# Easycheck_rev2_motherboard.net
KiCad netlist of a schematic drawn in EAGLE
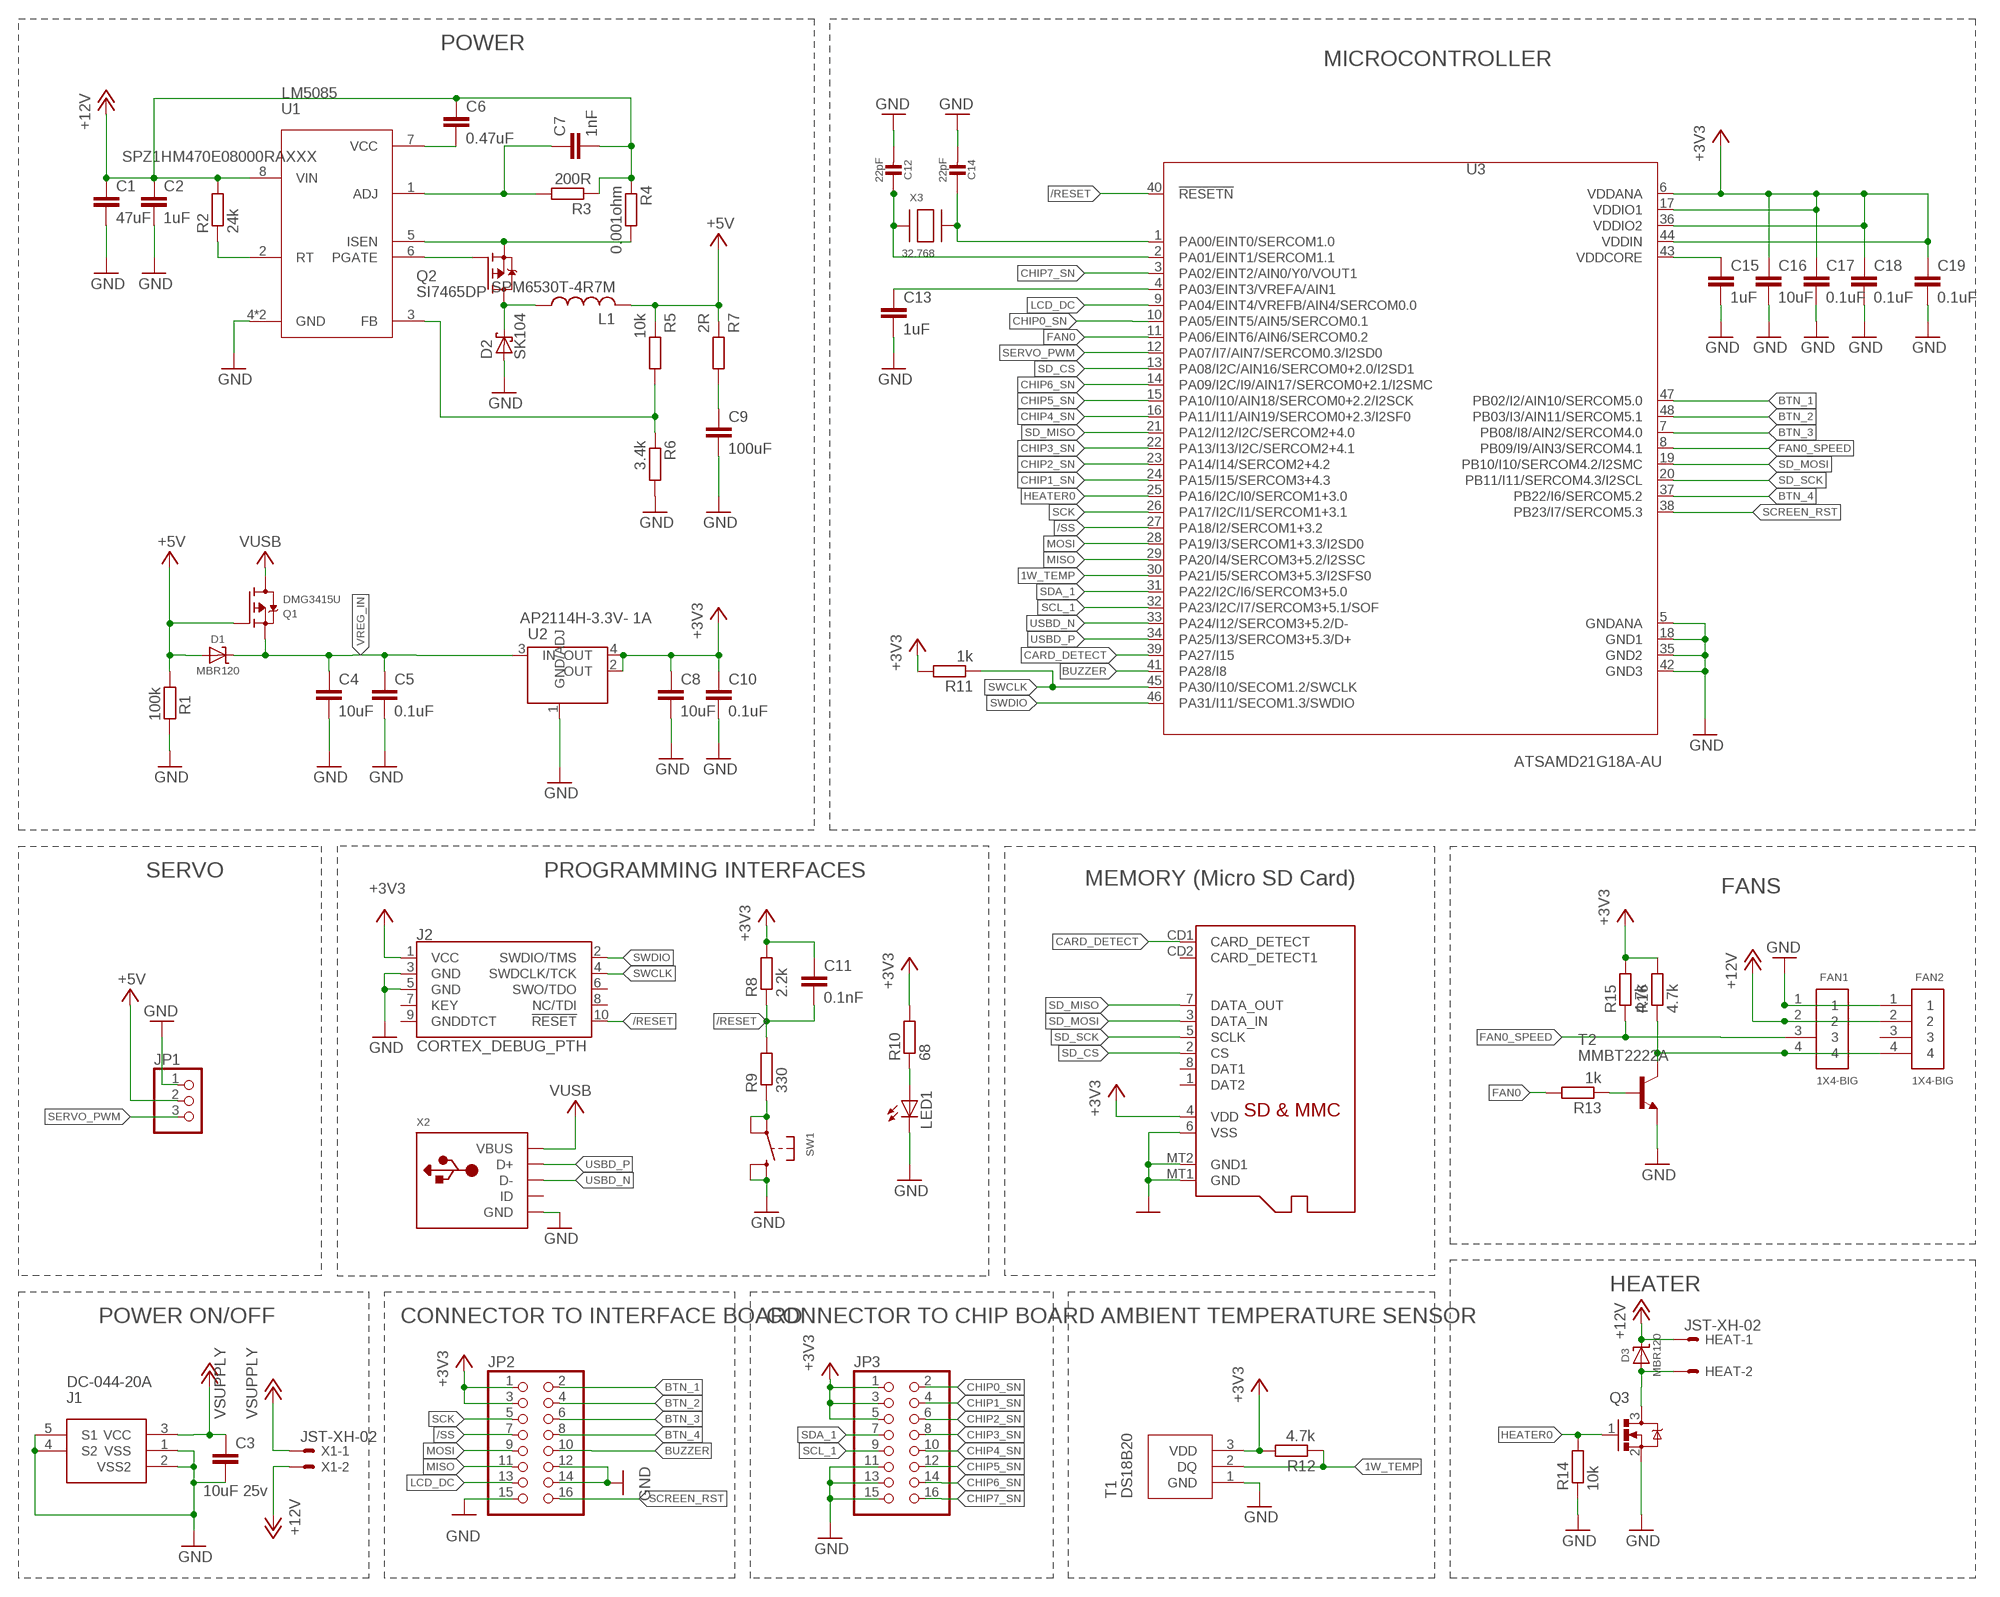
[diagram p0: schematic, sheet 1]

(export (version "E")
  (design (tool "Eeschema 10.0.6"))
  (components
    (comp (ref "C1")
      (value "47uF")
      (footprint "eagle-import:C1206")
      (libsource (lib "eagle-import") (part "C-EUC1206"))
    )
    (comp (ref "C2")
      (value "1uF")
      (footprint "eagle-import:C1206")
      (libsource (lib "eagle-import") (part "C-EUC1206"))
    )
    (comp (ref "C3")
      (value "10uF 25v")
      (footprint "eagle-import:C1206")
      (libsource (lib "eagle-import") (part "C-EUC1206"))
    )
    (comp (ref "C4")
      (value "10uF")
      (footprint "eagle-import:C0603")
      (libsource (lib "eagle-import") (part "C-EUC0603"))
    )
    (comp (ref "C5")
      (value "0.1uF")
      (footprint "eagle-import:C0603")
      (libsource (lib "eagle-import") (part "C-EUC0603"))
    )
    (comp (ref "C6")
      (value "0.47uF")
      (footprint "eagle-import:C1206")
      (libsource (lib "eagle-import") (part "C-EUC1206"))
    )
    (comp (ref "C7")
      (value "1nF")
      (footprint "eagle-import:C0603")
      (libsource (lib "eagle-import") (part "C-EUC0603"))
    )
    (comp (ref "C8")
      (value "10uF")
      (footprint "eagle-import:C0603")
      (libsource (lib "eagle-import") (part "C-EUC0603"))
    )
    (comp (ref "C9")
      (value "100uF")
      (footprint "eagle-import:C0805")
      (libsource (lib "eagle-import") (part "C-EUC0805"))
    )
    (comp (ref "C10")
      (value "0.1uF")
      (footprint "eagle-import:C0603")
      (libsource (lib "eagle-import") (part "C-EUC0603"))
    )
    (comp (ref "C11")
      (value "0.1nF")
      (footprint "eagle-import:C0603")
      (libsource (lib "eagle-import") (part "C-EUC0603"))
    )
    (comp (ref "C12")
      (value "22pF")
      (footprint "eagle-import:0603-NO@1")
      (libsource (lib "eagle-import") (part "CAP_CERAMIC0603_NO"))
    )
    (comp (ref "C13")
      (value "1uF")
      (footprint "eagle-import:C0603")
      (libsource (lib "eagle-import") (part "C-EUC0603"))
    )
    (comp (ref "C14")
      (value "22pF")
      (footprint "eagle-import:0603-NO@1")
      (libsource (lib "eagle-import") (part "CAP_CERAMIC0603_NO"))
    )
    (comp (ref "C15")
      (value "1uF")
      (footprint "eagle-import:C0603")
      (libsource (lib "eagle-import") (part "C-EUC0603"))
    )
    (comp (ref "C16")
      (value "10uF")
      (footprint "eagle-import:C0603")
      (libsource (lib "eagle-import") (part "C-EUC0603"))
    )
    (comp (ref "C17")
      (value "0.1uF")
      (footprint "eagle-import:C0603")
      (libsource (lib "eagle-import") (part "C-EUC0603"))
    )
    (comp (ref "C18")
      (value "0.1uF")
      (footprint "eagle-import:C0603")
      (libsource (lib "eagle-import") (part "C-EUC0603"))
    )
    (comp (ref "C19")
      (value "0.1uF")
      (footprint "eagle-import:C0603")
      (libsource (lib "eagle-import") (part "C-EUC0603"))
    )
    (comp (ref "D1")
      (value "MBR120")
      (footprint "eagle-import:MICROBUILDER_SOD-123")
      (libsource (lib "eagle-import") (part "MICROBUILDER_DIODE-SCHOTTKYSOD-123"))
    )
    (comp (ref "D2")
      (value "SK104")
      (footprint "eagle-import:SK104")
      (libsource (lib "eagle-import") (part "SK104"))
    )
    (comp (ref "D3")
      (value "MBR120")
      (footprint "eagle-import:MICROBUILDER_SOD-123")
      (libsource (lib "eagle-import") (part "MICROBUILDER_DIODE-SCHOTTKYSOD-123"))
    )
    (comp (ref "FAN1")
      (value "1X4-BIG")
      (footprint "eagle-import:1X04-BIG")
      (libsource (lib "eagle-import") (part "1X4-BIG"))
    )
    (comp (ref "FAN2")
      (value "1X4-BIG")
      (footprint "eagle-import:1X04-BIG")
      (libsource (lib "eagle-import") (part "1X4-BIG"))
    )
    (comp (ref "HEAT")
      (value "JST-XH-02")
      (footprint "eagle-import:JST-XH-02-PACKAGE-LONG-PAD")
      (libsource (lib "eagle-import") (part "JST-XH-02-PIN-LONG-PAD"))
    )
    (comp (ref "J1")
      (value "DC-044-20A")
      (footprint "eagle-import:DC-044-20A")
      (libsource (lib "eagle-import") (part "DC-044-20A"))
    )
    (comp (ref "J2")
      (value "CORTEX_DEBUG_PTH")
      (footprint "eagle-import:2X5-PTH-1.27MM")
      (libsource (lib "eagle-import") (part "CORTEX_DEBUG_PTH"))
    )
    (comp (ref "JP1")
      (value "PINHD-1X3")
      (footprint "eagle-import:1X03")
      (libsource (lib "eagle-import") (part "PINHD-1X3"))
    )
    (comp (ref "JP2")
      (value "PINHD-2X8")
      (footprint "eagle-import:2X08")
      (libsource (lib "eagle-import") (part "PINHD-2X8"))
    )
    (comp (ref "JP3")
      (value "PINHD-2X8")
      (footprint "eagle-import:2X08")
      (libsource (lib "eagle-import") (part "PINHD-2X8"))
    )
    (comp (ref "L1")
      (value "SPM6530T-4R7M")
      (footprint "eagle-import:SPM6530T-4R7M")
      (libsource (lib "eagle-import") (part "SPM6530T-4R7M"))
    )
    (comp (ref "LED1")
      (value "LEDCHIPLED_0603")
      (footprint "eagle-import:CHIPLED_0603")
      (libsource (lib "eagle-import") (part "LEDCHIPLED_0603"))
    )
    (comp (ref "Q1")
      (value "DMG3415U")
      (footprint "eagle-import:SOT23-R")
      (libsource (lib "eagle-import") (part "MOSFET-P"))
    )
    (comp (ref "Q2")
      (value "SI7465DP")
      (footprint "eagle-import:SI7465")
      (libsource (lib "eagle-import") (part "SI7465DP"))
    )
    (comp (ref "Q3")
      (value "DMN6140L")
      (footprint "eagle-import:SOT91P240X110-3N")
      (libsource (lib "eagle-import") (part "DMN6140L"))
    )
    (comp (ref "R1")
      (value "100k")
      (footprint "eagle-import:R0603")
      (libsource (lib "eagle-import") (part "R-EU_R0603"))
    )
    (comp (ref "R2")
      (value "24k")
      (footprint "eagle-import:R0603")
      (libsource (lib "eagle-import") (part "R-EU_R0603"))
    )
    (comp (ref "R3")
      (value "200R")
      (footprint "eagle-import:R0603")
      (libsource (lib "eagle-import") (part "R-EU_R0603"))
    )
    (comp (ref "R4")
      (value "0.001ohm")
      (footprint "eagle-import:R1206")
      (libsource (lib "eagle-import") (part "R-EU_R1206"))
    )
    (comp (ref "R5")
      (value "10k")
      (footprint "eagle-import:R0603")
      (libsource (lib "eagle-import") (part "R-EU_R0603"))
    )
    (comp (ref "R6")
      (value "3.4k")
      (footprint "eagle-import:R0603")
      (libsource (lib "eagle-import") (part "R-EU_R0603"))
    )
    (comp (ref "R7")
      (value "2R")
      (footprint "eagle-import:R0805")
      (libsource (lib "eagle-import") (part "R-EU_R0805"))
    )
    (comp (ref "R8")
      (value "2.2k")
      (footprint "eagle-import:R0603")
      (libsource (lib "eagle-import") (part "R-EU_R0603"))
    )
    (comp (ref "R9")
      (value "330")
      (footprint "eagle-import:R0603")
      (libsource (lib "eagle-import") (part "R-EU_R0603"))
    )
    (comp (ref "R10")
      (value "68")
      (footprint "eagle-import:R0603")
      (libsource (lib "eagle-import") (part "R-EU_R0603"))
    )
    (comp (ref "R11")
      (value "1k")
      (footprint "eagle-import:R0603")
      (libsource (lib "eagle-import") (part "R-EU_R0603"))
    )
    (comp (ref "R12")
      (value "4.7k")
      (footprint "eagle-import:R0603")
      (libsource (lib "eagle-import") (part "R-EU_R0603"))
    )
    (comp (ref "R13")
      (value "1k")
      (footprint "eagle-import:R0603")
      (libsource (lib "eagle-import") (part "R-EU_R0603"))
    )
    (comp (ref "R14")
      (value "10k")
      (footprint "eagle-import:R0603")
      (libsource (lib "eagle-import") (part "R-EU_R0603"))
    )
    (comp (ref "R15")
      (value "4.7k")
      (footprint "eagle-import:R0603")
      (libsource (lib "eagle-import") (part "R-EU_R0603"))
    )
    (comp (ref "R16")
      (value "4.7k")
      (footprint "eagle-import:R0603")
      (libsource (lib "eagle-import") (part "R-EU_R0603"))
    )
    (comp (ref "SD1")
      (value "MICROSD")
      (footprint "eagle-import:MICROSD")
      (libsource (lib "eagle-import") (part "MICROSD"))
    )
    (comp (ref "SW1")
      (value "MICROBUILDER_SWITCH_TACT_SMT_EVQQ2_SMALL")
      (footprint "eagle-import:MICROBUILDER_EVQ-Q2_SMALLER")
      (libsource (lib "eagle-import") (part "MICROBUILDER_SWITCH_TACT_SMT_EVQQ2_SMALL"))
    )
    (comp (ref "T1")
      (value "DS18B20")
      (footprint "eagle-import:TO92")
      (libsource (lib "eagle-import") (part "DS18B20"))
    )
    (comp (ref "T2")
      (value "MMBT2222A")
      (footprint "eagle-import:SOT23-BEC")
      (libsource (lib "eagle-import") (part "-NPN-SOT23-BECMMBT2222ALT1"))
    )
    (comp (ref "U1")
      (value "LM5085")
      (footprint "eagle-import:LM5085")
      (libsource (lib "eagle-import") (part "LM5085"))
    )
    (comp (ref "U2")
      (value "AP2114H-3.3V- 1A")
      (footprint "eagle-import:GEN_COMP_SOT223")
      (libsource (lib "eagle-import") (part "GEN_COMP_LINEAR_MC33269ST"))
    )
    (comp (ref "U3")
      (value "ATSAMD21G18A-AU")
      (footprint "eagle-import:QFP50P900X900X120-48N")
      (fields (field (name "MF") "Microchip"))
      (libsource (lib "eagle-import") (part "ATSAMD21G18A-AU"))
    )
    (comp (ref "X1")
      (value "JST-XH-02")
      (footprint "eagle-import:JST-XH-02-PACKAGE-LONG-PAD")
      (libsource (lib "eagle-import") (part "JST-XH-02-PIN-LONG-PAD"))
    )
    (comp (ref "X2")
      (value "MICROBUILDER_USB_MICRO_20329_V2")
      (footprint "eagle-import:MICROBUILDER_4UCONN_20329_V2")
      (libsource (lib "eagle-import") (part "MICROBUILDER_USB_MICRO_20329_V2"))
    )
    (comp (ref "X3")
      (value "32.768")
      (footprint "eagle-import:XTAL3215")
      (libsource (lib "eagle-import") (part "XTAL-3.2X1.5"))
    )
  )
  (nets
    (net (code "1") (name "+3V3") (class "Default")
      (node (ref "C10") (pin "1") (pinfunction "1_1") (pintype "passive"))
      (node (ref "C11") (pin "1") (pinfunction "1_1") (pintype "passive"))
      (node (ref "C16") (pin "1") (pinfunction "1_1") (pintype "passive"))
      (node (ref "C17") (pin "1") (pinfunction "1_1") (pintype "passive"))
      (node (ref "C18") (pin "1") (pinfunction "1_1") (pintype "passive"))
      (node (ref "C19") (pin "1") (pinfunction "1_1") (pintype "passive"))
      (node (ref "C8") (pin "1") (pinfunction "1_1") (pintype "passive"))
      (node (ref "J2") (pin "1") (pinfunction "VCC_1") (pintype "bidirectional"))
      (node (ref "JP2") (pin "1") (pinfunction "1_1") (pintype "passive"))
      (node (ref "JP2") (pin "3") (pinfunction "3_3") (pintype "passive"))
      (node (ref "JP3") (pin "1") (pinfunction "1_1") (pintype "passive"))
      (node (ref "JP3") (pin "3") (pinfunction "3_3") (pintype "passive"))
      (node (ref "JP3") (pin "5") (pinfunction "5_5") (pintype "passive"))
      (node (ref "R10") (pin "2") (pinfunction "2_2") (pintype "passive"))
      (node (ref "R11") (pin "2") (pinfunction "2_2") (pintype "passive"))
      (node (ref "R12") (pin "2") (pinfunction "2_2") (pintype "passive"))
      (node (ref "R15") (pin "2") (pinfunction "2_2") (pintype "passive"))
      (node (ref "R16") (pin "2") (pinfunction "2_2") (pintype "passive"))
      (node (ref "R8") (pin "2") (pinfunction "2_2") (pintype "passive"))
      (node (ref "SD1") (pin "4") (pinfunction "VDD_4") (pintype "power_in"))
      (node (ref "T1") (pin "3") (pinfunction "VDD_3") (pintype "bidirectional"))
      (node (ref "U2") (pin "2") (pinfunction "OUT_2") (pintype "passive"))
      (node (ref "U2") (pin "4") (pinfunction "OUT_4") (pintype "passive"))
      (node (ref "U3") (pin "17") (pinfunction "VDDIO1_17") (pintype "power_in"))
      (node (ref "U3") (pin "36") (pinfunction "VDDIO2_36") (pintype "power_in"))
      (node (ref "U3") (pin "44") (pinfunction "VDDIN_44") (pintype "power_in"))
      (node (ref "U3") (pin "6") (pinfunction "VDDANA_6") (pintype "power_in"))
    )
    (net (code "2") (name "+5V") (class "Default")
      (node (ref "D1") (pin "A") (pinfunction "A_A") (pintype "passive"))
      (node (ref "JP1") (pin "2") (pinfunction "2_2") (pintype "passive"))
      (node (ref "L1") (pin "2") (pinfunction "2_2") (pintype "passive"))
      (node (ref "Q1") (pin "1") (pinfunction "G_1") (pintype "passive"))
      (node (ref "R1") (pin "1") (pinfunction "1_1") (pintype "passive"))
      (node (ref "R5") (pin "1") (pinfunction "1_1") (pintype "passive"))
      (node (ref "R7") (pin "1") (pinfunction "1_1") (pintype "passive"))
    )
    (net (code "3") (name "+12V") (class "Default")
      (node (ref "C1") (pin "1") (pinfunction "1_1") (pintype "passive"))
      (node (ref "C2") (pin "1") (pinfunction "1_1") (pintype "passive"))
      (node (ref "C6") (pin "1") (pinfunction "1_1") (pintype "passive"))
      (node (ref "C7") (pin "2") (pinfunction "2_2") (pintype "passive"))
      (node (ref "D3") (pin "C") (pinfunction "C_C") (pintype "passive"))
      (node (ref "FAN1") (pin "2") (pinfunction "2_2") (pintype "bidirectional"))
      (node (ref "FAN2") (pin "2") (pinfunction "2_2") (pintype "bidirectional"))
      (node (ref "HEAT") (pin "1") (pinfunction "S_1") (pintype "passive"))
      (node (ref "R2") (pin "2") (pinfunction "2_2") (pintype "passive"))
      (node (ref "R3") (pin "1") (pinfunction "1_1") (pintype "passive"))
      (node (ref "R4") (pin "1") (pinfunction "1_1") (pintype "passive"))
      (node (ref "U1") (pin "8") (pinfunction "VIN_8") (pintype "bidirectional"))
      (node (ref "X1") (pin "2") (pinfunction "S_2") (pintype "passive"))
    )
    (net (code "4") (name "1W_TEMP") (class "Default")
      (node (ref "R12") (pin "1") (pinfunction "1_1") (pintype "passive"))
      (node (ref "T1") (pin "2") (pinfunction "DQ_2") (pintype "bidirectional"))
      (node (ref "U3") (pin "30") (pinfunction "PA21/I5/SERCOM3+5.3/I2SFS0_30") (pintype "bidirectional"))
    )
    (net (code "5") (name "BTN_1") (class "Default")
      (node (ref "JP2") (pin "2") (pinfunction "2_2") (pintype "passive"))
      (node (ref "U3") (pin "47") (pinfunction "PB02/I2/AIN10/SERCOM5.0_47") (pintype "bidirectional"))
    )
    (net (code "6") (name "BTN_2") (class "Default")
      (node (ref "JP2") (pin "4") (pinfunction "4_4") (pintype "passive"))
      (node (ref "U3") (pin "48") (pinfunction "PB03/I3/AIN11/SERCOM5.1_48") (pintype "bidirectional"))
    )
    (net (code "7") (name "BTN_3") (class "Default")
      (node (ref "JP2") (pin "6") (pinfunction "6_6") (pintype "passive"))
      (node (ref "U3") (pin "7") (pinfunction "PB08/I8/AIN2/SERCOM4.0_7") (pintype "bidirectional"))
    )
    (net (code "8") (name "BTN_4") (class "Default")
      (node (ref "JP2") (pin "8") (pinfunction "8_8") (pintype "passive"))
      (node (ref "U3") (pin "37") (pinfunction "PB22/I6/SERCOM5.2_37") (pintype "bidirectional"))
    )
    (net (code "9") (name "BUZZER") (class "Default")
      (node (ref "JP2") (pin "10") (pinfunction "10_10") (pintype "passive"))
      (node (ref "U3") (pin "41") (pinfunction "PA28/I8_41") (pintype "bidirectional"))
    )
    (net (code "10") (name "CARD_DETECT") (class "Default")
      (node (ref "SD1") (pin "CD1") (pinfunction "CARD_DETECT_CD1") (pintype "passive"))
      (node (ref "U3") (pin "39") (pinfunction "PA27/I15_39") (pintype "bidirectional"))
    )
    (net (code "11") (name "CHIP0_SN") (class "Default")
      (node (ref "JP3") (pin "2") (pinfunction "2_2") (pintype "passive"))
      (node (ref "U3") (pin "10") (pinfunction "PA05/EINT5/AIN5/SERCOM0.1_10") (pintype "bidirectional"))
    )
    (net (code "12") (name "CHIP1_SN") (class "Default")
      (node (ref "JP3") (pin "4") (pinfunction "4_4") (pintype "passive"))
      (node (ref "U3") (pin "24") (pinfunction "PA15/I15/SERCOM3+4.3_24") (pintype "bidirectional"))
    )
    (net (code "13") (name "CHIP2_SN") (class "Default")
      (node (ref "JP3") (pin "6") (pinfunction "6_6") (pintype "passive"))
      (node (ref "U3") (pin "23") (pinfunction "PA14/I14/SERCOM2+4.2_23") (pintype "bidirectional"))
    )
    (net (code "14") (name "CHIP3_SN") (class "Default")
      (node (ref "JP3") (pin "8") (pinfunction "8_8") (pintype "passive"))
      (node (ref "U3") (pin "22") (pinfunction "PA13/I13/I2C/SERCOM2+4.1_22") (pintype "bidirectional"))
    )
    (net (code "15") (name "CHIP4_SN") (class "Default")
      (node (ref "JP3") (pin "10") (pinfunction "10_10") (pintype "passive"))
      (node (ref "U3") (pin "16") (pinfunction "PA11/I11/AIN19/SERCOM0+2.3/I2SF0_16") (pintype "bidirectional"))
    )
    (net (code "16") (name "CHIP5_SN") (class "Default")
      (node (ref "JP3") (pin "12") (pinfunction "12_12") (pintype "passive"))
      (node (ref "U3") (pin "15") (pinfunction "PA10/I10/AIN18/SERCOM0+2.2/I2SCK_15") (pintype "bidirectional"))
    )
    (net (code "17") (name "CHIP6_SN") (class "Default")
      (node (ref "JP3") (pin "14") (pinfunction "14_14") (pintype "passive"))
      (node (ref "U3") (pin "14") (pinfunction "PA09/I2C/I9/AIN17/SERCOM0+2.1/I2SMC_14") (pintype "bidirectional"))
    )
    (net (code "18") (name "CHIP7_SN") (class "Default")
      (node (ref "JP3") (pin "16") (pinfunction "16_16") (pintype "passive"))
      (node (ref "U3") (pin "3") (pinfunction "PA02/EINT2/AIN0/Y0/VOUT1_3") (pintype "bidirectional"))
    )
    (net (code "19") (name "FAN0") (class "Default")
      (node (ref "R13") (pin "2") (pinfunction "2_2") (pintype "passive"))
      (node (ref "U3") (pin "11") (pinfunction "PA06/EINT6/AIN6/SERCOM0.2_11") (pintype "bidirectional"))
    )
    (net (code "20") (name "FAN0_SPEED") (class "Default")
      (node (ref "FAN1") (pin "3") (pinfunction "3_3") (pintype "bidirectional"))
      (node (ref "R15") (pin "1") (pinfunction "1_1") (pintype "passive"))
      (node (ref "U3") (pin "8") (pinfunction "PB09/I9/AIN3/SERCOM4.1_8") (pintype "bidirectional"))
    )
    (net (code "21") (name "GND") (class "Default")
      (node (ref "C1") (pin "2") (pinfunction "2_2") (pintype "passive"))
      (node (ref "C10") (pin "2") (pinfunction "2_2") (pintype "passive"))
      (node (ref "C12") (pin "2") (pinfunction "2_2") (pintype "passive"))
      (node (ref "C13") (pin "2") (pinfunction "2_2") (pintype "passive"))
      (node (ref "C14") (pin "2") (pinfunction "2_2") (pintype "passive"))
      (node (ref "C15") (pin "2") (pinfunction "2_2") (pintype "passive"))
      (node (ref "C16") (pin "2") (pinfunction "2_2") (pintype "passive"))
      (node (ref "C17") (pin "2") (pinfunction "2_2") (pintype "passive"))
      (node (ref "C18") (pin "2") (pinfunction "2_2") (pintype "passive"))
      (node (ref "C19") (pin "2") (pinfunction "2_2") (pintype "passive"))
      (node (ref "C2") (pin "2") (pinfunction "2_2") (pintype "passive"))
      (node (ref "C3") (pin "2") (pinfunction "2_2") (pintype "passive"))
      (node (ref "C4") (pin "2") (pinfunction "2_2") (pintype "passive"))
      (node (ref "C5") (pin "2") (pinfunction "2_2") (pintype "passive"))
      (node (ref "C8") (pin "2") (pinfunction "2_2") (pintype "passive"))
      (node (ref "C9") (pin "2") (pinfunction "2_2") (pintype "passive"))
      (node (ref "D2") (pin "1") (pinfunction "A_1") (pintype "passive"))
      (node (ref "FAN1") (pin "1") (pinfunction "1_1") (pintype "bidirectional"))
      (node (ref "FAN2") (pin "1") (pinfunction "1_1") (pintype "bidirectional"))
      (node (ref "J1") (pin "1") (pinfunction "VSS_1") (pintype "bidirectional"))
      (node (ref "J1") (pin "2") (pinfunction "VSS2_2") (pintype "bidirectional"))
      (node (ref "J1") (pin "4") (pinfunction "S2_4") (pintype "bidirectional"))
      (node (ref "J1") (pin "5") (pinfunction "S1_5") (pintype "bidirectional"))
      (node (ref "J2") (pin "3") (pinfunction "GND_3") (pintype "bidirectional"))
      (node (ref "J2") (pin "5") (pinfunction "GND_5") (pintype "bidirectional"))
      (node (ref "JP1") (pin "1") (pinfunction "1_1") (pintype "passive"))
      (node (ref "JP2") (pin "12") (pinfunction "12_12") (pintype "passive"))
      (node (ref "JP2") (pin "14") (pinfunction "14_14") (pintype "passive"))
      (node (ref "JP2") (pin "15") (pinfunction "15_15") (pintype "passive"))
      (node (ref "JP3") (pin "11") (pinfunction "11_11") (pintype "passive"))
      (node (ref "JP3") (pin "13") (pinfunction "13_13") (pintype "passive"))
      (node (ref "JP3") (pin "15") (pinfunction "15_15") (pintype "passive"))
      (node (ref "LED1") (pin "C") (pinfunction "C_C") (pintype "passive"))
      (node (ref "Q3") (pin "2") (pinfunction "2_2") (pintype "bidirectional"))
      (node (ref "R1") (pin "2") (pinfunction "2_2") (pintype "passive"))
      (node (ref "R14") (pin "1") (pinfunction "1_1") (pintype "passive"))
      (node (ref "R6") (pin "2") (pinfunction "2_2") (pintype "passive"))
      (node (ref "SD1") (pin "6") (pinfunction "VSS_6") (pintype "power_in"))
      (node (ref "SD1") (pin "MT1") (pinfunction "GND_MT1") (pintype "power_in"))
      (node (ref "SD1") (pin "MT2") (pinfunction "GND1_MT2") (pintype "power_in"))
      (node (ref "SW1") (pin "B") (pinfunction "S_B") (pintype "passive"))
      (node (ref "SW1") (pin "B'") (pinfunction "S1_B'") (pintype "passive"))
      (node (ref "T1") (pin "1") (pinfunction "GND_1") (pintype "bidirectional"))
      (node (ref "T2") (pin "E") (pinfunction "E_E") (pintype "passive"))
      (node (ref "U1") (pin "4") (pinfunction "GND_4") (pintype "bidirectional"))
      (node (ref "U1") (pin "9") (pinfunction "GND_9") (pintype "bidirectional"))
      (node (ref "U2") (pin "1") (pinfunction "GND/ADJ_1") (pintype "input"))
      (node (ref "U3") (pin "18") (pinfunction "GND1_18") (pintype "power_in"))
      (node (ref "U3") (pin "35") (pinfunction "GND2_35") (pintype "power_in"))
      (node (ref "U3") (pin "42") (pinfunction "GND3_42") (pintype "power_in"))
      (node (ref "U3") (pin "5") (pinfunction "GNDANA_5") (pintype "power_in"))
      (node (ref "X2") (pin "BASE@1") (pinfunction "GND_BASE@1") (pintype "power_in"))
      (node (ref "X2") (pin "BASE@2") (pinfunction "GND_BASE@2") (pintype "power_in"))
      (node (ref "X2") (pin "GND") (pinfunction "GND_GND") (pintype "power_in"))
      (node (ref "X2") (pin "SPRT@1") (pinfunction "GND_SPRT@1") (pintype "power_in"))
      (node (ref "X2") (pin "SPRT@2") (pinfunction "GND_SPRT@2") (pintype "power_in"))
      (node (ref "X2") (pin "SPRT@3") (pinfunction "GND_SPRT@3") (pintype "power_in"))
      (node (ref "X2") (pin "SPRT@4") (pinfunction "GND_SPRT@4") (pintype "power_in"))
    )
    (net (code "22") (name "HEATER0") (class "Default")
      (node (ref "Q3") (pin "1") (pinfunction "1_1") (pintype "bidirectional"))
      (node (ref "R14") (pin "2") (pinfunction "2_2") (pintype "passive"))
      (node (ref "U3") (pin "25") (pinfunction "PA16/I2C/I0/SERCOM1+3.0_25") (pintype "bidirectional"))
    )
    (net (code "23") (name "LCD_DC") (class "Default")
      (node (ref "JP2") (pin "13") (pinfunction "13_13") (pintype "passive"))
      (node (ref "U3") (pin "9") (pinfunction "PA04/EINT4/VREFB/AIN4/SERCOM0.0_9") (pintype "bidirectional"))
    )
    (net (code "24") (name "MISO") (class "Default")
      (node (ref "JP2") (pin "11") (pinfunction "11_11") (pintype "passive"))
      (node (ref "U3") (pin "29") (pinfunction "PA20/I4/SERCOM3+5.2/I2SSC_29") (pintype "bidirectional"))
    )
    (net (code "25") (name "MOSI") (class "Default")
      (node (ref "JP2") (pin "9") (pinfunction "9_9") (pintype "passive"))
      (node (ref "U3") (pin "28") (pinfunction "PA19/I3/SERCOM1+3.3/I2SD0_28") (pintype "bidirectional"))
    )
    (net (code "26") (name "Net-(C9-Pad1)") (class "Default")
      (node (ref "C9") (pin "1") (pinfunction "1_1") (pintype "passive"))
      (node (ref "R7") (pin "2") (pinfunction "2_2") (pintype "passive"))
    )
    (net (code "27") (name "Net-(D2-C)") (class "Default")
      (node (ref "D2") (pin "2") (pinfunction "C_2") (pintype "passive"))
      (node (ref "L1") (pin "1") (pinfunction "1_1") (pintype "passive"))
      (node (ref "Q2") (pin "5") (pinfunction "D_5") (pintype "passive"))
      (node (ref "Q2") (pin "6") (pinfunction "D_6") (pintype "passive"))
      (node (ref "Q2") (pin "7") (pinfunction "D_7") (pintype "passive"))
      (node (ref "Q2") (pin "8") (pinfunction "D_8") (pintype "passive"))
      (node (ref "Q2") (pin "9") (pinfunction "D_9") (pintype "passive"))
    )
    (net (code "28") (name "Net-(FAN1-Pad4)") (class "Default")
      (node (ref "FAN1") (pin "4") (pinfunction "4_4") (pintype "bidirectional"))
      (node (ref "FAN2") (pin "4") (pinfunction "4_4") (pintype "bidirectional"))
      (node (ref "R16") (pin "1") (pinfunction "1_1") (pintype "passive"))
      (node (ref "T2") (pin "C") (pinfunction "C_C") (pintype "passive"))
    )
    (net (code "29") (name "Net-(HEATB-S)") (class "Default")
      (node (ref "D3") (pin "A") (pinfunction "A_A") (pintype "passive"))
      (node (ref "HEAT") (pin "2") (pinfunction "S_2") (pintype "passive"))
      (node (ref "Q3") (pin "3") (pinfunction "3_3") (pintype "bidirectional"))
    )
    (net (code "30") (name "Net-(LED1-PadA)") (class "Default")
      (node (ref "LED1") (pin "A") (pinfunction "A_A") (pintype "passive"))
      (node (ref "R10") (pin "1") (pinfunction "1_1") (pintype "passive"))
    )
    (net (code "31") (name "Net-(Q2-G)") (class "Default")
      (node (ref "Q2") (pin "4") (pinfunction "G_4") (pintype "passive"))
      (node (ref "U1") (pin "6") (pinfunction "PGATE_6") (pintype "bidirectional"))
    )
    (net (code "32") (name "Net-(R13-Pad1)") (class "Default")
      (node (ref "R13") (pin "1") (pinfunction "1_1") (pintype "passive"))
      (node (ref "T2") (pin "B") (pinfunction "B_B") (pintype "passive"))
    )
    (net (code "33") (name "Net-(SW1-P)") (class "Default")
      (node (ref "R9") (pin "1") (pinfunction "1_1") (pintype "passive"))
      (node (ref "SW1") (pin "A") (pinfunction "P_A") (pintype "passive"))
      (node (ref "SW1") (pin "A'") (pinfunction "P1_A'") (pintype "passive"))
    )
    (net (code "34") (name "Net-(U1-ADJ)") (class "Default")
      (node (ref "C7") (pin "1") (pinfunction "1_1") (pintype "passive"))
      (node (ref "R3") (pin "2") (pinfunction "2_2") (pintype "passive"))
      (node (ref "U1") (pin "1") (pinfunction "ADJ_1") (pintype "bidirectional"))
    )
    (net (code "35") (name "Net-(U1-FB)") (class "Default")
      (node (ref "R5") (pin "2") (pinfunction "2_2") (pintype "passive"))
      (node (ref "R6") (pin "1") (pinfunction "1_1") (pintype "passive"))
      (node (ref "U1") (pin "3") (pinfunction "FB_3") (pintype "bidirectional"))
    )
    (net (code "36") (name "Net-(U1-ISEN)") (class "Default")
      (node (ref "Q2") (pin "1") (pinfunction "S_1") (pintype "passive"))
      (node (ref "Q2") (pin "2") (pinfunction "S_2") (pintype "passive"))
      (node (ref "Q2") (pin "3") (pinfunction "S_3") (pintype "passive"))
      (node (ref "R4") (pin "2") (pinfunction "2_2") (pintype "passive"))
      (node (ref "U1") (pin "5") (pinfunction "ISEN_5") (pintype "bidirectional"))
    )
    (net (code "37") (name "Net-(U1-RT)") (class "Default")
      (node (ref "R2") (pin "1") (pinfunction "1_1") (pintype "passive"))
      (node (ref "U1") (pin "2") (pinfunction "RT_2") (pintype "bidirectional"))
    )
    (net (code "38") (name "Net-(U1-VCC)") (class "Default")
      (node (ref "C6") (pin "2") (pinfunction "2_2") (pintype "passive"))
      (node (ref "U1") (pin "7") (pinfunction "VCC_7") (pintype "bidirectional"))
    )
    (net (code "39") (name "Net-(U3-PA00{slash}EINT0{slash}SERCOM1.0)") (class "Default")
      (node (ref "C14") (pin "1") (pinfunction "1_1") (pintype "passive"))
      (node (ref "U3") (pin "1") (pinfunction "PA00/EINT0/SERCOM1.0_1") (pintype "bidirectional"))
      (node (ref "X3") (pin "P$2") (pinfunction "P$2_P$2") (pintype "bidirectional"))
    )
    (net (code "40") (name "Net-(U3-PA01{slash}EINT1{slash}SERCOM1.1)") (class "Default")
      (node (ref "C12") (pin "1") (pinfunction "1_1") (pintype "passive"))
      (node (ref "U3") (pin "2") (pinfunction "PA01/EINT1/SERCOM1.1_2") (pintype "bidirectional"))
      (node (ref "X3") (pin "P$1") (pinfunction "P$1_P$1") (pintype "bidirectional"))
    )
    (net (code "41") (name "Net-(U3-PA03{slash}EINT3{slash}VREFA{slash}AIN1)") (class "Default")
      (node (ref "C13") (pin "1") (pinfunction "1_1") (pintype "passive"))
      (node (ref "U3") (pin "4") (pinfunction "PA03/EINT3/VREFA/AIN1_4") (pintype "bidirectional"))
    )
    (net (code "42") (name "Net-(U3-VDDCORE)") (class "Default")
      (node (ref "C15") (pin "1") (pinfunction "1_1") (pintype "passive"))
      (node (ref "U3") (pin "43") (pinfunction "VDDCORE_43") (pintype "power_in"))
    )
    (net (code "43") (name "SCK") (class "Default")
      (node (ref "JP2") (pin "5") (pinfunction "5_5") (pintype "passive"))
      (node (ref "U3") (pin "26") (pinfunction "PA17/I2C/I1/SERCOM1+3.1_26") (pintype "bidirectional"))
    )
    (net (code "44") (name "SCL_1") (class "Default")
      (node (ref "JP3") (pin "9") (pinfunction "9_9") (pintype "passive"))
      (node (ref "U3") (pin "32") (pinfunction "PA23/I2C/I7/SERCOM3+5.1/SOF_32") (pintype "bidirectional"))
    )
    (net (code "45") (name "SCREEN_RST") (class "Default")
      (node (ref "JP2") (pin "16") (pinfunction "16_16") (pintype "passive"))
      (node (ref "U3") (pin "38") (pinfunction "PB23/I7/SERCOM5.3_38") (pintype "bidirectional"))
    )
    (net (code "46") (name "SDA_1") (class "Default")
      (node (ref "JP3") (pin "7") (pinfunction "7_7") (pintype "passive"))
      (node (ref "U3") (pin "31") (pinfunction "PA22/I2C/I6/SERCOM3+5.0_31") (pintype "bidirectional"))
    )
    (net (code "47") (name "SD_CS") (class "Default")
      (node (ref "SD1") (pin "2") (pinfunction "CS_2") (pintype "input"))
      (node (ref "U3") (pin "13") (pinfunction "PA08/I2C/AIN16/SERCOM0+2.0/I2SD1_13") (pintype "bidirectional"))
    )
    (net (code "48") (name "SD_MISO") (class "Default")
      (node (ref "SD1") (pin "7") (pinfunction "DATA_OUT_7") (pintype "output"))
      (node (ref "U3") (pin "21") (pinfunction "PA12/I12/I2C/SERCOM2+4.0_21") (pintype "bidirectional"))
    )
    (net (code "49") (name "SD_MOSI") (class "Default")
      (node (ref "SD1") (pin "3") (pinfunction "DATA_IN_3") (pintype "input"))
      (node (ref "U3") (pin "19") (pinfunction "PB10/I10/SERCOM4.2/I2SMC_19") (pintype "bidirectional"))
    )
    (net (code "50") (name "SD_SCK") (class "Default")
      (node (ref "SD1") (pin "5") (pinfunction "SCLK_5") (pintype "input"))
      (node (ref "U3") (pin "20") (pinfunction "PB11/I11/SERCOM4.3/I2SCL_20") (pintype "bidirectional"))
    )
    (net (code "51") (name "SERVO_PWM") (class "Default")
      (node (ref "JP1") (pin "3") (pinfunction "3_3") (pintype "passive"))
      (node (ref "U3") (pin "12") (pinfunction "PA07/I7/AIN7/SERCOM0.3/I2SD0_12") (pintype "bidirectional"))
    )
    (net (code "52") (name "SWCLK") (class "Default")
      (node (ref "J2") (pin "4") (pinfunction "SWDCLK/TCK_4") (pintype "bidirectional"))
      (node (ref "R11") (pin "1") (pinfunction "1_1") (pintype "passive"))
      (node (ref "U3") (pin "45") (pinfunction "PA30/I10/SECOM1.2/SWCLK_45") (pintype "bidirectional"))
    )
    (net (code "53") (name "SWDIO") (class "Default")
      (node (ref "J2") (pin "2") (pinfunction "SWDIO/TMS_2") (pintype "bidirectional"))
      (node (ref "U3") (pin "46") (pinfunction "PA31/I11/SECOM1.3/SWDIO_46") (pintype "bidirectional"))
    )
    (net (code "54") (name "USBD_N") (class "Default")
      (node (ref "U3") (pin "33") (pinfunction "PA24/I12/SERCOM3+5.2/D-_33") (pintype "bidirectional"))
      (node (ref "X2") (pin "D-") (pinfunction "D-_D-") (pintype "bidirectional"))
    )
    (net (code "55") (name "USBD_P") (class "Default")
      (node (ref "U3") (pin "34") (pinfunction "PA25/I13/SERCOM3+5.3/D+_34") (pintype "bidirectional"))
      (node (ref "X2") (pin "D+") (pinfunction "D+_D+") (pintype "bidirectional"))
    )
    (net (code "56") (name "VREG_IN") (class "Default")
      (node (ref "C4") (pin "1") (pinfunction "1_1") (pintype "passive"))
      (node (ref "C5") (pin "1") (pinfunction "1_1") (pintype "passive"))
      (node (ref "D1") (pin "C") (pinfunction "C_C") (pintype "passive"))
      (node (ref "Q1") (pin "2") (pinfunction "S_2") (pintype "passive"))
      (node (ref "U2") (pin "3") (pinfunction "IN_3") (pintype "input"))
    )
    (net (code "57") (name "VSUPPLY") (class "Default")
      (node (ref "C3") (pin "1") (pinfunction "1_1") (pintype "passive"))
      (node (ref "J1") (pin "3") (pinfunction "VCC_3") (pintype "bidirectional"))
      (node (ref "X1") (pin "1") (pinfunction "S_1") (pintype "passive"))
    )
    (net (code "58") (name "VUSB") (class "Default")
      (node (ref "Q1") (pin "3") (pinfunction "D_3") (pintype "passive"))
      (node (ref "X2") (pin "VBUS") (pinfunction "VBUS_VBUS") (pintype "power_in"))
    )
    (net (code "59") (name "unconnected-(FAN2-Pad3)") (class "Default")
      (node (ref "FAN2") (pin "3") (pinfunction "3_3") (pintype "bidirectional"))
    )
    (net (code "60") (name "unconnected-(J2-GNDDTCT-Pad9)") (class "Default")
      (node (ref "J2") (pin "9") (pinfunction "GNDDTCT_9") (pintype "bidirectional"))
    )
    (net (code "61") (name "unconnected-(J2-KEY-Pad7)") (class "Default")
      (node (ref "J2") (pin "7") (pinfunction "KEY_7") (pintype "bidirectional"))
    )
    (net (code "62") (name "unconnected-(J2-NC{slash}TDI-Pad8)") (class "Default")
      (node (ref "J2") (pin "8") (pinfunction "NC/TDI_8") (pintype "bidirectional"))
    )
    (net (code "63") (name "unconnected-(J2-SWO{slash}TDO-Pad6)") (class "Default")
      (node (ref "J2") (pin "6") (pinfunction "SWO/TDO_6") (pintype "bidirectional"))
    )
    (net (code "64") (name "unconnected-(SD1-CARD_DETECT1-PadCD2)") (class "Default")
      (node (ref "SD1") (pin "CD2") (pinfunction "CARD_DETECT1_CD2") (pintype "passive"))
    )
    (net (code "65") (name "unconnected-(SD1-DAT1-Pad8)") (class "Default")
      (node (ref "SD1") (pin "8") (pinfunction "DAT1_8") (pintype "bidirectional"))
    )
    (net (code "66") (name "unconnected-(SD1-DAT2-Pad1)") (class "Default")
      (node (ref "SD1") (pin "1") (pinfunction "DAT2_1") (pintype "bidirectional"))
    )
    (net (code "67") (name "unconnected-(X2-PadID)") (class "Default")
      (node (ref "X2") (pin "ID") (pinfunction "ID_ID") (pintype "bidirectional"))
    )
    (net (code "68") (name "{slash}RESET") (class "Default")
      (node (ref "C11") (pin "2") (pinfunction "2_2") (pintype "passive"))
      (node (ref "J2") (pin "10") (pinfunction "~{RESET}_10") (pintype "bidirectional"))
      (node (ref "R8") (pin "1") (pinfunction "1_1") (pintype "passive"))
      (node (ref "R9") (pin "2") (pinfunction "2_2") (pintype "passive"))
      (node (ref "U3") (pin "40") (pinfunction "~{RESETN}_40") (pintype "input"))
    )
    (net (code "69") (name "{slash}SS") (class "Default")
      (node (ref "JP2") (pin "7") (pinfunction "7_7") (pintype "passive"))
      (node (ref "U3") (pin "27") (pinfunction "PA18/I2/SERCOM1+3.2_27") (pintype "bidirectional"))
    )
  )
)
